# LMT01_Interface.net
KiCad netlist of a schematic drawn in Altium Designer
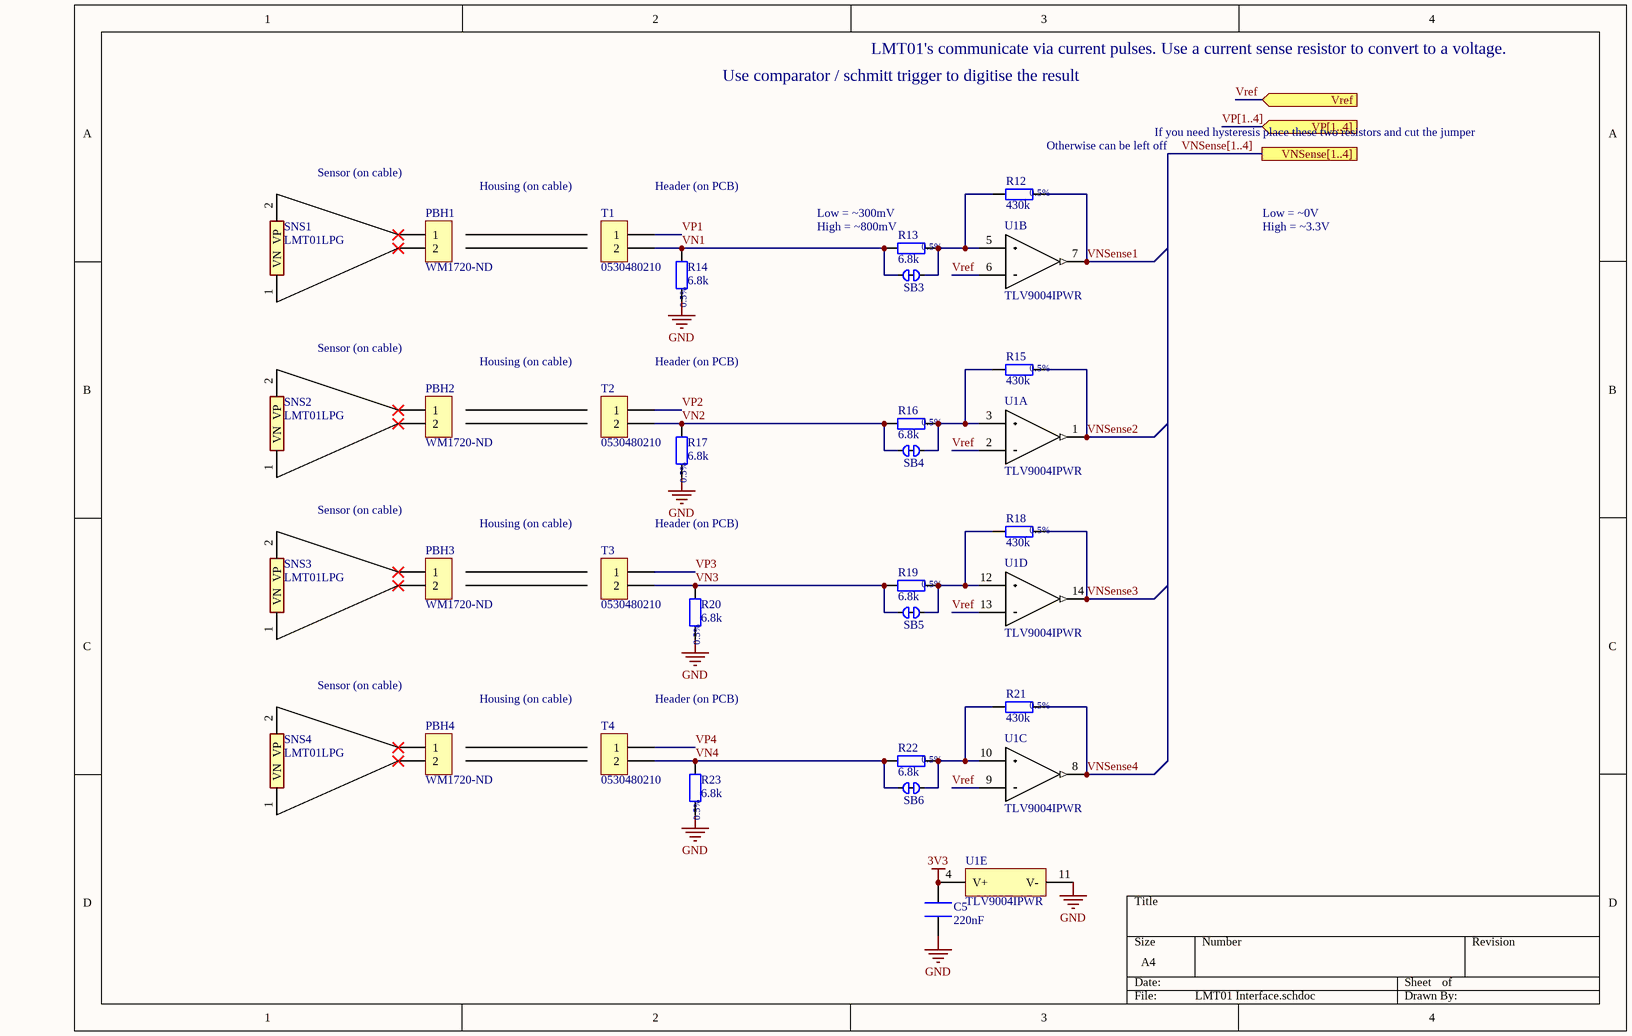
[diagram p0: LMT01 Interface.schdoc]

(export (version "E")
  (design (tool "Eeschema 10.0.6"))
  (components
    (comp (ref "C5")
      (value "220nF")
      (footprint "APSS Prototype Parts:CAPACITOR_0805_2012M-70N")
      (fields
        (field (name "TOLERANCE") "±10%")
        (field (name "MF PART NO.") "C0805C224K1RAC7800")
        (field (name "APSS STANDARD PART") "APSS Standard")
      )
      (libsource (lib "APSS Prototype Parts") (part "C0805C224K1RAC7800"))
    )
    (comp (ref "PBH1")
      (value "0530480210")
      (description "Housing - Picoblade 02-pin, TH, RA")
      (fields (field (name "APSS STANDARD PART") "APSS Standard") (field (name "MF PART NO.") "WM1720-ND"))
      (libsource (lib "") (part "0530480210_1"))
    )
    (comp (ref "PBH2")
      (value "0530480210")
      (description "Housing - Picoblade 02-pin, TH, RA")
      (fields (field (name "APSS STANDARD PART") "APSS Standard") (field (name "MF PART NO.") "WM1720-ND"))
      (libsource (lib "") (part "0530480210_1"))
    )
    (comp (ref "PBH3")
      (value "0530480210")
      (description "Housing - Picoblade 02-pin, TH, RA")
      (fields (field (name "APSS STANDARD PART") "APSS Standard") (field (name "MF PART NO.") "WM1720-ND"))
      (libsource (lib "") (part "0530480210_1"))
    )
    (comp (ref "PBH4")
      (value "0530480210")
      (description "Housing - Picoblade 02-pin, TH, RA")
      (fields (field (name "APSS STANDARD PART") "APSS Standard") (field (name "MF PART NO.") "WM1720-ND"))
      (libsource (lib "") (part "0530480210_1"))
    )
    (comp (ref "R12")
      (value "430k")
      (footprint "APSS Prototype Parts:Resistor_0805_2012M-50N")
      (fields
        (field (name "TOLERANCE") "0.5%")
        (field (name "POWER") "1/8W")
        (field (name "APSS STANDARD PART") "APSS Standard")
      )
      (libsource (lib "APSS Prototype Parts") (part "RG2012P-xxx-D-T5 Series"))
    )
    (comp (ref "R13")
      (value "6.8k")
      (footprint "APSS Prototype Parts:Resistor_0805_2012M-50N")
      (fields
        (field (name "TOLERANCE") "0.5%")
        (field (name "POWER") "1/8W")
        (field (name "APSS STANDARD PART") "APSS Standard")
      )
      (libsource (lib "APSS Prototype Parts") (part "RG2012P-xxx-D-T5 Series"))
    )
    (comp (ref "R14")
      (value "6.8k")
      (footprint "APSS Prototype Parts:Resistor_0805_2012M-50N")
      (fields
        (field (name "TOLERANCE") "0.5%")
        (field (name "POWER") "1/8W")
        (field (name "APSS STANDARD PART") "APSS Standard")
      )
      (libsource (lib "") (part "RG2012P-xxx-D-T5 Series_1"))
    )
    (comp (ref "R15")
      (value "430k")
      (footprint "APSS Prototype Parts:Resistor_0805_2012M-50N")
      (fields
        (field (name "TOLERANCE") "0.5%")
        (field (name "POWER") "1/8W")
        (field (name "APSS STANDARD PART") "APSS Standard")
      )
      (libsource (lib "APSS Prototype Parts") (part "RG2012P-xxx-D-T5 Series"))
    )
    (comp (ref "R16")
      (value "6.8k")
      (footprint "APSS Prototype Parts:Resistor_0805_2012M-50N")
      (fields
        (field (name "TOLERANCE") "0.5%")
        (field (name "POWER") "1/8W")
        (field (name "APSS STANDARD PART") "APSS Standard")
      )
      (libsource (lib "APSS Prototype Parts") (part "RG2012P-xxx-D-T5 Series"))
    )
    (comp (ref "R17")
      (value "6.8k")
      (footprint "APSS Prototype Parts:Resistor_0805_2012M-50N")
      (fields
        (field (name "TOLERANCE") "0.5%")
        (field (name "POWER") "1/8W")
        (field (name "APSS STANDARD PART") "APSS Standard")
      )
      (libsource (lib "") (part "RG2012P-xxx-D-T5 Series_1"))
    )
    (comp (ref "R18")
      (value "430k")
      (footprint "APSS Prototype Parts:Resistor_0805_2012M-50N")
      (fields
        (field (name "TOLERANCE") "0.5%")
        (field (name "POWER") "1/8W")
        (field (name "APSS STANDARD PART") "APSS Standard")
      )
      (libsource (lib "APSS Prototype Parts") (part "RG2012P-xxx-D-T5 Series"))
    )
    (comp (ref "R19")
      (value "6.8k")
      (footprint "APSS Prototype Parts:Resistor_0805_2012M-50N")
      (fields
        (field (name "TOLERANCE") "0.5%")
        (field (name "POWER") "1/8W")
        (field (name "APSS STANDARD PART") "APSS Standard")
      )
      (libsource (lib "APSS Prototype Parts") (part "RG2012P-xxx-D-T5 Series"))
    )
    (comp (ref "R20")
      (value "6.8k")
      (footprint "APSS Prototype Parts:Resistor_0805_2012M-50N")
      (fields
        (field (name "TOLERANCE") "0.5%")
        (field (name "POWER") "1/8W")
        (field (name "APSS STANDARD PART") "APSS Standard")
      )
      (libsource (lib "") (part "RG2012P-xxx-D-T5 Series_1"))
    )
    (comp (ref "R21")
      (value "430k")
      (footprint "APSS Prototype Parts:Resistor_0805_2012M-50N")
      (fields
        (field (name "TOLERANCE") "0.5%")
        (field (name "POWER") "1/8W")
        (field (name "APSS STANDARD PART") "APSS Standard")
      )
      (libsource (lib "APSS Prototype Parts") (part "RG2012P-xxx-D-T5 Series"))
    )
    (comp (ref "R22")
      (value "6.8k")
      (footprint "APSS Prototype Parts:Resistor_0805_2012M-50N")
      (fields
        (field (name "TOLERANCE") "0.5%")
        (field (name "POWER") "1/8W")
        (field (name "APSS STANDARD PART") "APSS Standard")
      )
      (libsource (lib "APSS Prototype Parts") (part "RG2012P-xxx-D-T5 Series"))
    )
    (comp (ref "R23")
      (value "6.8k")
      (footprint "APSS Prototype Parts:Resistor_0805_2012M-50N")
      (fields
        (field (name "TOLERANCE") "0.5%")
        (field (name "POWER") "1/8W")
        (field (name "APSS STANDARD PART") "APSS Standard")
      )
      (libsource (lib "") (part "RG2012P-xxx-D-T5 Series_1"))
    )
    (comp (ref "SB3")
      (value "Solder Jumper Normally Closed 0201")
      (footprint "General Components:Solder Bridge Closed 0201")
      (libsource (lib "General Components") (part "Solder Jumper Normally Closed 0201"))
    )
    (comp (ref "SB4")
      (value "Solder Jumper Normally Closed 0201")
      (footprint "General Components:Solder Bridge Closed 0201")
      (libsource (lib "General Components") (part "Solder Jumper Normally Closed 0201"))
    )
    (comp (ref "SB5")
      (value "Solder Jumper Normally Closed 0201")
      (footprint "General Components:Solder Bridge Closed 0201")
      (libsource (lib "General Components") (part "Solder Jumper Normally Closed 0201"))
    )
    (comp (ref "SB6")
      (value "Solder Jumper Normally Closed 0201")
      (footprint "General Components:Solder Bridge Closed 0201")
      (libsource (lib "General Components") (part "Solder Jumper Normally Closed 0201"))
    )
    (comp (ref "SNS1")
      (value "LMT01LPG")
      (footprint "LPG0002A")
      (description "0.5Â°C Accurate 2-pin Temperature Sensor with a Pulse Train Interface")
      (libsource (lib "LMT01LPG") (part "LMT01LPG"))
    )
    (comp (ref "SNS2")
      (value "LMT01LPG")
      (footprint "LPG0002A")
      (description "0.5Â°C Accurate 2-pin Temperature Sensor with a Pulse Train Interface")
      (libsource (lib "LMT01LPG") (part "LMT01LPG"))
    )
    (comp (ref "SNS3")
      (value "LMT01LPG")
      (footprint "LPG0002A")
      (description "0.5Â°C Accurate 2-pin Temperature Sensor with a Pulse Train Interface")
      (libsource (lib "LMT01LPG") (part "LMT01LPG"))
    )
    (comp (ref "SNS4")
      (value "LMT01LPG")
      (footprint "LPG0002A")
      (description "0.5Â°C Accurate 2-pin Temperature Sensor with a Pulse Train Interface")
      (libsource (lib "LMT01LPG") (part "LMT01LPG"))
    )
    (comp (ref "T1")
      (value "0530480210")
      (footprint "APSS Prototype Parts:MOLEX_0530480210")
      (description "Header - Picoblade 02-pin, TH, RA")
      (fields (field (name "APSS STANDARD PART") "APSS Standard") (field (name "MF PART NO.") "0530480210"))
      (libsource (lib "APSS Prototype Parts") (part "0530480210"))
    )
    (comp (ref "T2")
      (value "0530480210")
      (footprint "APSS Prototype Parts:MOLEX_0530480210")
      (description "Header - Picoblade 02-pin, TH, RA")
      (fields (field (name "APSS STANDARD PART") "APSS Standard") (field (name "MF PART NO.") "0530480210"))
      (libsource (lib "APSS Prototype Parts") (part "0530480210"))
    )
    (comp (ref "T3")
      (value "0530480210")
      (footprint "APSS Prototype Parts:MOLEX_0530480210")
      (description "Header - Picoblade 02-pin, TH, RA")
      (fields (field (name "APSS STANDARD PART") "APSS Standard") (field (name "MF PART NO.") "0530480210"))
      (libsource (lib "APSS Prototype Parts") (part "0530480210"))
    )
    (comp (ref "T4")
      (value "0530480210")
      (footprint "APSS Prototype Parts:MOLEX_0530480210")
      (description "Header - Picoblade 02-pin, TH, RA")
      (fields (field (name "APSS STANDARD PART") "APSS Standard") (field (name "MF PART NO.") "0530480210"))
      (libsource (lib "APSS Prototype Parts") (part "0530480210"))
    )
    (comp (ref "U1")
      (value "TLV9004IPWR")
      (footprint "APSS Prototype Parts:TSSOP65P640X120-14N")
      (description "IC - Opamp, Low Power, 4-Channel, 1MHz GBWP, RRIO, 1.8V to 5.5V, -40 to 125, 14-TSSOP")
      (fields (field (name "APSS STANDARD PART") "APSS Standard"))
      (libsource (lib "APSS Prototype Parts") (part "TLV9004IPWR"))
    )
  )
  (nets
    (net (code "1") (name "/VN1") (class "Default")
      (node (ref "R13") (pin "2") (pinfunction "2_2") (pintype "passive"))
      (node (ref "R14") (pin "2") (pinfunction "2_2") (pintype "passive"))
      (node (ref "SB3") (pin "2") (pinfunction "2_2") (pintype "passive"))
      (node (ref "T1") (pin "2") (pinfunction "2_2") (pintype "passive"))
    )
    (net (code "2") (name "/VN2") (class "Default")
      (node (ref "R16") (pin "2") (pinfunction "2_2") (pintype "passive"))
      (node (ref "R17") (pin "2") (pinfunction "2_2") (pintype "passive"))
      (node (ref "SB4") (pin "2") (pinfunction "2_2") (pintype "passive"))
      (node (ref "T2") (pin "2") (pinfunction "2_2") (pintype "passive"))
    )
    (net (code "3") (name "/VN3") (class "Default")
      (node (ref "R19") (pin "2") (pinfunction "2_2") (pintype "passive"))
      (node (ref "R20") (pin "2") (pinfunction "2_2") (pintype "passive"))
      (node (ref "SB5") (pin "2") (pinfunction "2_2") (pintype "passive"))
      (node (ref "T3") (pin "2") (pinfunction "2_2") (pintype "passive"))
    )
    (net (code "4") (name "/VN4") (class "Default")
      (node (ref "R22") (pin "2") (pinfunction "2_2") (pintype "passive"))
      (node (ref "R23") (pin "2") (pinfunction "2_2") (pintype "passive"))
      (node (ref "SB6") (pin "2") (pinfunction "2_2") (pintype "passive"))
      (node (ref "T4") (pin "2") (pinfunction "2_2") (pintype "passive"))
    )
    (net (code "5") (name "/VNSense1") (class "Default")
      (node (ref "R12") (pin "1") (pinfunction "1_1") (pintype "passive"))
      (node (ref "U1") (pin "7") (pinfunction "OUT2_7") (pintype "output"))
    )
    (net (code "6") (name "/VNSense2") (class "Default")
      (node (ref "R15") (pin "1") (pinfunction "1_1") (pintype "passive"))
      (node (ref "U1") (pin "1") (pinfunction "OUT1_1") (pintype "output"))
    )
    (net (code "7") (name "/VNSense3") (class "Default")
      (node (ref "R18") (pin "1") (pinfunction "1_1") (pintype "passive"))
      (node (ref "U1") (pin "14") (pinfunction "OUT4_14") (pintype "output"))
    )
    (net (code "8") (name "/VNSense4") (class "Default")
      (node (ref "R21") (pin "1") (pinfunction "1_1") (pintype "passive"))
      (node (ref "U1") (pin "8") (pinfunction "OUT3_8") (pintype "output"))
    )
    (net (code "10") (name "/VP1") (class "Default")
      (node (ref "T1") (pin "1") (pinfunction "1_1") (pintype "passive"))
    )
    (net (code "11") (name "/VP2") (class "Default")
      (node (ref "T2") (pin "1") (pinfunction "1_1") (pintype "passive"))
    )
    (net (code "12") (name "/VP3") (class "Default")
      (node (ref "T3") (pin "1") (pinfunction "1_1") (pintype "passive"))
    )
    (net (code "13") (name "/VP4") (class "Default")
      (node (ref "T4") (pin "1") (pinfunction "1_1") (pintype "passive"))
    )
    (net (code "15") (name "/Vref") (class "Default")
      (node (ref "U1") (pin "13") (pinfunction "IN4-_13") (pintype "passive"))
      (node (ref "U1") (pin "2") (pinfunction "IN1-_2") (pintype "passive"))
      (node (ref "U1") (pin "6") (pinfunction "IN2-_6") (pintype "passive"))
      (node (ref "U1") (pin "9") (pinfunction "IN3-_9") (pintype "passive"))
    )
    (net (code "16") (name "3V3") (class "Default")
      (node (ref "C5") (pin "2") (pinfunction "2_2") (pintype "passive"))
      (node (ref "U1") (pin "4") (pinfunction "V+_4") (pintype "power_in"))
    )
    (net (code "17") (name "GND") (class "Default")
      (node (ref "C5") (pin "1") (pinfunction "1_1") (pintype "passive"))
      (node (ref "R14") (pin "1") (pinfunction "1_1") (pintype "passive"))
      (node (ref "R17") (pin "1") (pinfunction "1_1") (pintype "passive"))
      (node (ref "R20") (pin "1") (pinfunction "1_1") (pintype "passive"))
      (node (ref "R23") (pin "1") (pinfunction "1_1") (pintype "passive"))
      (node (ref "U1") (pin "11") (pinfunction "V-_11") (pintype "power_in"))
    )
    (net (code "18") (name "Net-(U1A-IN1+)") (class "Default")
      (node (ref "R15") (pin "2") (pinfunction "2_2") (pintype "passive"))
      (node (ref "R16") (pin "1") (pinfunction "1_1") (pintype "passive"))
      (node (ref "SB4") (pin "1") (pinfunction "1_1") (pintype "passive"))
      (node (ref "U1") (pin "3") (pinfunction "IN1+_3") (pintype "passive"))
    )
    (net (code "19") (name "Net-(U1B-IN2+)") (class "Default")
      (node (ref "R12") (pin "2") (pinfunction "2_2") (pintype "passive"))
      (node (ref "R13") (pin "1") (pinfunction "1_1") (pintype "passive"))
      (node (ref "SB3") (pin "1") (pinfunction "1_1") (pintype "passive"))
      (node (ref "U1") (pin "5") (pinfunction "IN2+_5") (pintype "passive"))
    )
    (net (code "20") (name "Net-(U1C-IN3+)") (class "Default")
      (node (ref "R21") (pin "2") (pinfunction "2_2") (pintype "passive"))
      (node (ref "R22") (pin "1") (pinfunction "1_1") (pintype "passive"))
      (node (ref "SB6") (pin "1") (pinfunction "1_1") (pintype "passive"))
      (node (ref "U1") (pin "10") (pinfunction "IN3+_10") (pintype "passive"))
    )
    (net (code "21") (name "Net-(U1D-IN4+)") (class "Default")
      (node (ref "R18") (pin "2") (pinfunction "2_2") (pintype "passive"))
      (node (ref "R19") (pin "1") (pinfunction "1_1") (pintype "passive"))
      (node (ref "SB5") (pin "1") (pinfunction "1_1") (pintype "passive"))
      (node (ref "U1") (pin "12") (pinfunction "IN4+_12") (pintype "passive"))
    )
    (net (code "22") (name "unconnected-(PBH1-Pad1)") (class "Default")
      (node (ref "PBH1") (pin "1") (pinfunction "1_1") (pintype "passive+no_connect"))
    )
    (net (code "23") (name "unconnected-(PBH1-Pad2)") (class "Default")
      (node (ref "PBH1") (pin "2") (pinfunction "2_2") (pintype "passive+no_connect"))
    )
    (net (code "24") (name "unconnected-(PBH2-Pad1)") (class "Default")
      (node (ref "PBH2") (pin "1") (pinfunction "1_1") (pintype "passive+no_connect"))
    )
    (net (code "25") (name "unconnected-(PBH2-Pad2)") (class "Default")
      (node (ref "PBH2") (pin "2") (pinfunction "2_2") (pintype "passive+no_connect"))
    )
    (net (code "26") (name "unconnected-(PBH3-Pad1)") (class "Default")
      (node (ref "PBH3") (pin "1") (pinfunction "1_1") (pintype "passive+no_connect"))
    )
    (net (code "27") (name "unconnected-(PBH3-Pad2)") (class "Default")
      (node (ref "PBH3") (pin "2") (pinfunction "2_2") (pintype "passive+no_connect"))
    )
    (net (code "28") (name "unconnected-(PBH4-Pad1)") (class "Default")
      (node (ref "PBH4") (pin "1") (pinfunction "1_1") (pintype "passive+no_connect"))
    )
    (net (code "29") (name "unconnected-(PBH4-Pad2)") (class "Default")
      (node (ref "PBH4") (pin "2") (pinfunction "2_2") (pintype "passive+no_connect"))
    )
    (net (code "30") (name "unconnected-(SNS1-VN-Pad1)") (class "Default")
      (node (ref "SNS1") (pin "1") (pinfunction "VN_1") (pintype "passive"))
    )
    (net (code "31") (name "unconnected-(SNS1-VP-Pad2)") (class "Default")
      (node (ref "SNS1") (pin "2") (pinfunction "VP_2") (pintype "passive"))
    )
    (net (code "32") (name "unconnected-(SNS2-VN-Pad1)") (class "Default")
      (node (ref "SNS2") (pin "1") (pinfunction "VN_1") (pintype "passive"))
    )
    (net (code "33") (name "unconnected-(SNS2-VP-Pad2)") (class "Default")
      (node (ref "SNS2") (pin "2") (pinfunction "VP_2") (pintype "passive"))
    )
    (net (code "34") (name "unconnected-(SNS3-VN-Pad1)") (class "Default")
      (node (ref "SNS3") (pin "1") (pinfunction "VN_1") (pintype "passive"))
    )
    (net (code "35") (name "unconnected-(SNS3-VP-Pad2)") (class "Default")
      (node (ref "SNS3") (pin "2") (pinfunction "VP_2") (pintype "passive"))
    )
    (net (code "36") (name "unconnected-(SNS4-VN-Pad1)") (class "Default")
      (node (ref "SNS4") (pin "1") (pinfunction "VN_1") (pintype "passive"))
    )
    (net (code "37") (name "unconnected-(SNS4-VP-Pad2)") (class "Default")
      (node (ref "SNS4") (pin "2") (pinfunction "VP_2") (pintype "passive"))
    )
  )
)
